# P8_AudioOutput.net
KiCad netlist of a schematic drawn in Altium Designer
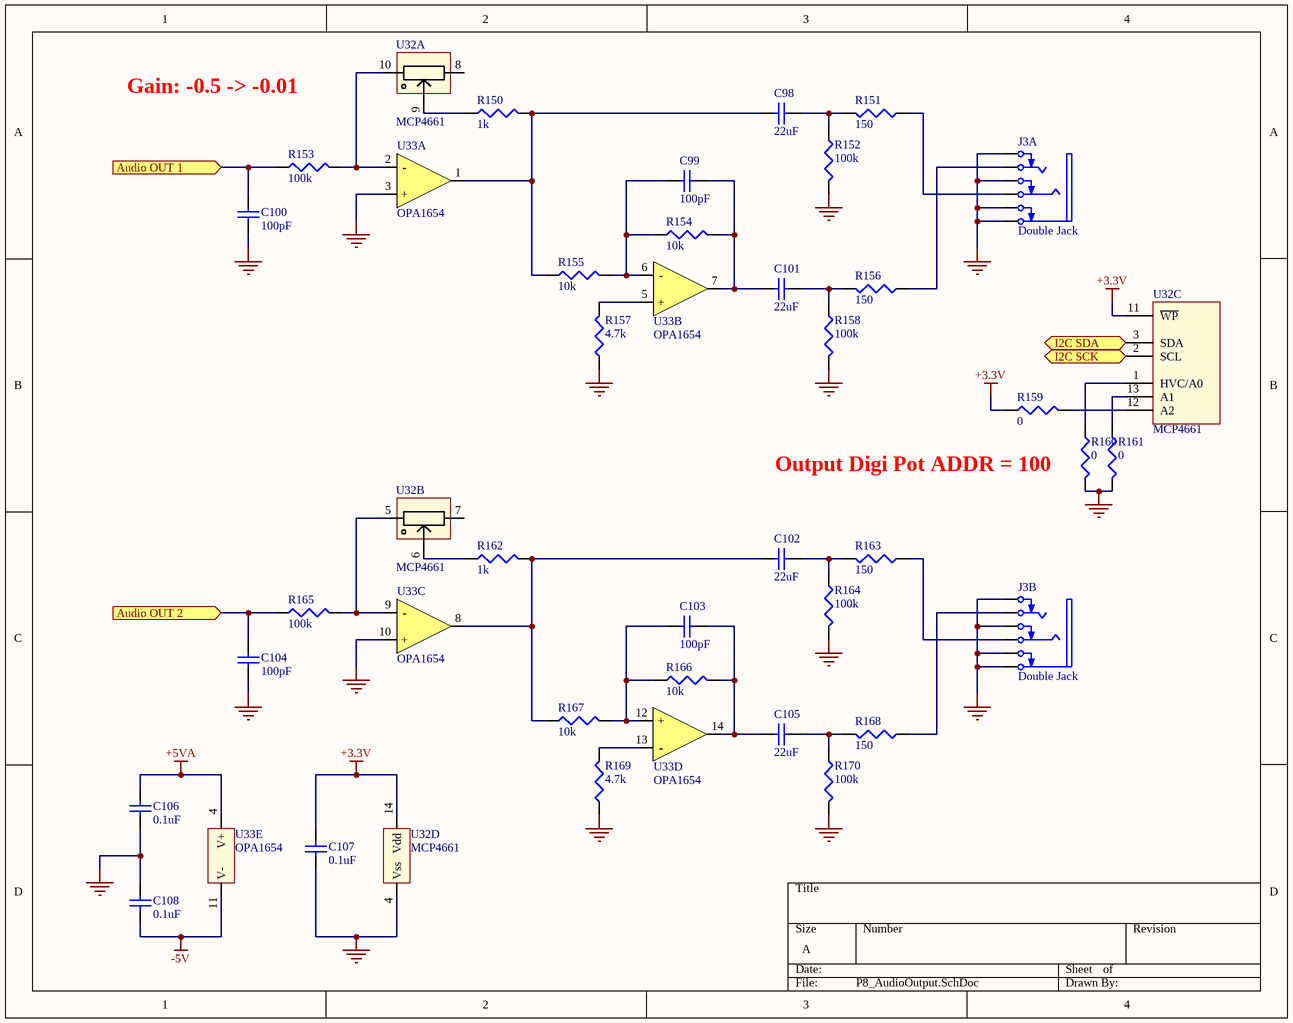
[diagram p0: P8_AudioOutput.SchDoc]

(export (version "E")
  (design (tool "Eeschema 10.0.6"))
  (components
    (comp (ref "C98")
      (value "22uF")
      (footprint "CAP 0603 (1608 metric)")
      (description "Capacitor (Semiconductor SIM Model)")
      (libsource (lib "Miscellaneous Devices") (part "Cap Semi"))
    )
    (comp (ref "C99")
      (value "100pF")
      (footprint "CAP 0603 (1608 metric)")
      (description "Capacitor (Semiconductor SIM Model)")
      (libsource (lib "Miscellaneous Devices") (part "Cap Semi"))
    )
    (comp (ref "C100")
      (value "100pF")
      (footprint "CAP 0603 (1608 metric)")
      (description "Capacitor (Semiconductor SIM Model)")
      (libsource (lib "Miscellaneous Devices") (part "Cap Semi"))
    )
    (comp (ref "C101")
      (value "22uF")
      (footprint "CAP 0603 (1608 metric)")
      (description "Capacitor (Semiconductor SIM Model)")
      (libsource (lib "Miscellaneous Devices") (part "Cap Semi"))
    )
    (comp (ref "C102")
      (value "22uF")
      (footprint "CAP 0603 (1608 metric)")
      (description "Capacitor (Semiconductor SIM Model)")
      (libsource (lib "Miscellaneous Devices") (part "Cap Semi"))
    )
    (comp (ref "C103")
      (value "100pF")
      (footprint "CAP 0603 (1608 metric)")
      (description "Capacitor (Semiconductor SIM Model)")
      (libsource (lib "Miscellaneous Devices") (part "Cap Semi"))
    )
    (comp (ref "C104")
      (value "100pF")
      (footprint "CAP 0603 (1608 metric)")
      (description "Capacitor (Semiconductor SIM Model)")
      (libsource (lib "Miscellaneous Devices") (part "Cap Semi"))
    )
    (comp (ref "C105")
      (value "22uF")
      (footprint "CAP 0603 (1608 metric)")
      (description "Capacitor (Semiconductor SIM Model)")
      (libsource (lib "Miscellaneous Devices") (part "Cap Semi"))
    )
    (comp (ref "C106")
      (value "0.1uF")
      (footprint "CAP 0603 (1608 metric)")
      (description "Capacitor (Semiconductor SIM Model)")
      (libsource (lib "Miscellaneous Devices") (part "Cap Semi"))
    )
    (comp (ref "C107")
      (value "0.1uF")
      (footprint "CAP 0603 (1608 metric)")
      (description "Capacitor (Semiconductor SIM Model)")
      (libsource (lib "Miscellaneous Devices") (part "Cap Semi"))
    )
    (comp (ref "C108")
      (value "0.1uF")
      (footprint "CAP 0603 (1608 metric)")
      (description "Capacitor (Semiconductor SIM Model)")
      (libsource (lib "Miscellaneous Devices") (part "Cap Semi"))
    )
    (comp (ref "J3")
      (value "Double Jack")
      (description "Dual Jack stereo bypassed")
      (libsource (lib "FilterPoC") (part "Dual TRS Jack Bypassed"))
    )
    (comp (ref "R150")
      (value "1k")
      (footprint "RES 0603 (1608 metric)")
      (description "Resistor")
      (libsource (lib "Miscellaneous Devices") (part "Res3"))
    )
    (comp (ref "R151")
      (value "150")
      (footprint "RES 0603 (1608 metric)")
      (description "Resistor")
      (libsource (lib "Miscellaneous Devices") (part "Res3"))
    )
    (comp (ref "R152")
      (value "100k")
      (footprint "RES 0603 (1608 metric)")
      (description "Resistor")
      (libsource (lib "Miscellaneous Devices") (part "Res3"))
    )
    (comp (ref "R153")
      (value "100k")
      (footprint "RES 0603 (1608 metric)")
      (description "Resistor")
      (libsource (lib "Miscellaneous Devices") (part "Res3"))
    )
    (comp (ref "R154")
      (value "10k")
      (footprint "RES 0603 (1608 metric)")
      (description "Resistor")
      (libsource (lib "Miscellaneous Devices") (part "Res3"))
    )
    (comp (ref "R155")
      (value "10k")
      (footprint "RES 0603 (1608 metric)")
      (description "Resistor")
      (libsource (lib "Miscellaneous Devices") (part "Res3"))
    )
    (comp (ref "R156")
      (value "150")
      (footprint "RES 0603 (1608 metric)")
      (description "Resistor")
      (libsource (lib "Miscellaneous Devices") (part "Res3"))
    )
    (comp (ref "R157")
      (value "4.7k")
      (footprint "RES 0603 (1608 metric)")
      (description "Resistor")
      (libsource (lib "Miscellaneous Devices") (part "Res3"))
    )
    (comp (ref "R158")
      (value "100k")
      (footprint "RES 0603 (1608 metric)")
      (description "Resistor")
      (libsource (lib "Miscellaneous Devices") (part "Res3"))
    )
    (comp (ref "R159")
      (value "0")
      (footprint "RES 0603 (1608 metric)")
      (description "Resistor")
      (libsource (lib "Miscellaneous Devices") (part "Res3"))
    )
    (comp (ref "R160")
      (value "0")
      (footprint "RES 0603 (1608 metric)")
      (description "Resistor")
      (libsource (lib "Miscellaneous Devices") (part "Res3"))
    )
    (comp (ref "R161")
      (value "0")
      (footprint "RES 0603 (1608 metric)")
      (description "Resistor")
      (libsource (lib "Miscellaneous Devices") (part "Res3"))
    )
    (comp (ref "R162")
      (value "1k")
      (footprint "RES 0603 (1608 metric)")
      (description "Resistor")
      (libsource (lib "Miscellaneous Devices") (part "Res3"))
    )
    (comp (ref "R163")
      (value "150")
      (footprint "RES 0603 (1608 metric)")
      (description "Resistor")
      (libsource (lib "Miscellaneous Devices") (part "Res3"))
    )
    (comp (ref "R164")
      (value "100k")
      (footprint "RES 0603 (1608 metric)")
      (description "Resistor")
      (libsource (lib "Miscellaneous Devices") (part "Res3"))
    )
    (comp (ref "R165")
      (value "100k")
      (footprint "RES 0603 (1608 metric)")
      (description "Resistor")
      (libsource (lib "Miscellaneous Devices") (part "Res3"))
    )
    (comp (ref "R166")
      (value "10k")
      (footprint "RES 0603 (1608 metric)")
      (description "Resistor")
      (libsource (lib "Miscellaneous Devices") (part "Res3"))
    )
    (comp (ref "R167")
      (value "10k")
      (footprint "RES 0603 (1608 metric)")
      (description "Resistor")
      (libsource (lib "Miscellaneous Devices") (part "Res3"))
    )
    (comp (ref "R168")
      (value "150")
      (footprint "RES 0603 (1608 metric)")
      (description "Resistor")
      (libsource (lib "Miscellaneous Devices") (part "Res3"))
    )
    (comp (ref "R169")
      (value "4.7k")
      (footprint "RES 0603 (1608 metric)")
      (description "Resistor")
      (libsource (lib "Miscellaneous Devices") (part "Res3"))
    )
    (comp (ref "R170")
      (value "100k")
      (footprint "RES 0603 (1608 metric)")
      (description "Resistor")
      (libsource (lib "Miscellaneous Devices") (part "Res3"))
    )
    (comp (ref "U32")
      (value "MCP4661")
      (description "Dual DigiPot non volatile I2C")
      (libsource (lib "FilterPoC") (part "MCP4661"))
    )
    (comp (ref "U33")
      (value "OPA1654")
      (description "Quad Audio OpAmp")
      (libsource (lib "") (part "OPA1654_1"))
    )
  )
  (nets
    (net (code "1") (name "+3.3V") (class "Default")
      (node (ref "C107") (pin "1") (pinfunction "1_1") (pintype "passive"))
      (node (ref "R159") (pin "1") (pinfunction "1_1") (pintype "passive"))
      (node (ref "U32") (pin "11") (pinfunction "~{WP}_11") (pintype "passive"))
      (node (ref "U32") (pin "14") (pinfunction "Vdd_14") (pintype "power_in"))
    )
    (net (code "2") (name "+5VA") (class "Default")
      (node (ref "C106") (pin "1") (pinfunction "1_1") (pintype "passive"))
      (node (ref "U33") (pin "4") (pinfunction "V+_4") (pintype "power_in"))
    )
    (net (code "3") (name "-5V") (class "Default")
      (node (ref "C108") (pin "2") (pinfunction "2_2") (pintype "passive"))
      (node (ref "U33") (pin "11") (pinfunction "V-_11") (pintype "power_in"))
    )
    (net (code "4") (name "/Audio OUT 1") (class "Default")
      (node (ref "C100") (pin "2") (pinfunction "2_2") (pintype "passive"))
      (node (ref "R153") (pin "1") (pinfunction "1_1") (pintype "passive"))
    )
    (net (code "5") (name "/Audio OUT 2") (class "Default")
      (node (ref "C104") (pin "2") (pinfunction "2_2") (pintype "passive"))
      (node (ref "R165") (pin "1") (pinfunction "1_1") (pintype "passive"))
    )
    (net (code "6") (name "/I2C SCK") (class "Default")
      (node (ref "U32") (pin "2") (pinfunction "SCL_2") (pintype "passive"))
    )
    (net (code "7") (name "/I2C SDA") (class "Default")
      (node (ref "U32") (pin "3") (pinfunction "SDA_3") (pintype "passive"))
    )
    (net (code "8") (name "GND") (class "Default")
      (node (ref "C100") (pin "1") (pinfunction "1_1") (pintype "passive"))
      (node (ref "C104") (pin "1") (pinfunction "1_1") (pintype "passive"))
      (node (ref "C106") (pin "2") (pinfunction "2_2") (pintype "passive"))
      (node (ref "C107") (pin "2") (pinfunction "2_2") (pintype "passive"))
      (node (ref "C108") (pin "1") (pinfunction "1_1") (pintype "passive"))
      (node (ref "J3") (pin "1") (pinfunction "SB_1") (pintype "passive"))
      (node (ref "J3") (pin "10") (pinfunction "S_10") (pintype "power_in"))
      (node (ref "J3") (pin "2") (pinfunction "RB_2") (pintype "passive"))
      (node (ref "J3") (pin "3") (pinfunction "TB_3") (pintype "passive"))
      (node (ref "J3") (pin "4") (pinfunction "S_4") (pintype "power_in"))
      (node (ref "J3") (pin "7") (pinfunction "SB_7") (pintype "passive"))
      (node (ref "J3") (pin "8") (pinfunction "RB_8") (pintype "passive"))
      (node (ref "J3") (pin "9") (pinfunction "TB_9") (pintype "passive"))
      (node (ref "R152") (pin "2") (pinfunction "2_2") (pintype "passive"))
      (node (ref "R157") (pin "1") (pinfunction "1_1") (pintype "passive"))
      (node (ref "R158") (pin "2") (pinfunction "2_2") (pintype "passive"))
      (node (ref "R160") (pin "2") (pinfunction "2_2") (pintype "passive"))
      (node (ref "R161") (pin "2") (pinfunction "2_2") (pintype "passive"))
      (node (ref "R164") (pin "2") (pinfunction "2_2") (pintype "passive"))
      (node (ref "R169") (pin "1") (pinfunction "1_1") (pintype "passive"))
      (node (ref "R170") (pin "2") (pinfunction "2_2") (pintype "passive"))
      (node (ref "U32") (pin "4") (pinfunction "Vss_4") (pintype "power_in"))
      (node (ref "U33") (pin "10") (pinfunction "+_10") (pintype "passive"))
      (node (ref "U33") (pin "3") (pinfunction "+_3") (pintype "passive"))
    )
    (net (code "9") (name "Net-(C98-Pad1)") (class "Default")
      (node (ref "C98") (pin "1") (pinfunction "1_1") (pintype "passive"))
      (node (ref "R151") (pin "2") (pinfunction "2_2") (pintype "passive"))
      (node (ref "R152") (pin "1") (pinfunction "1_1") (pintype "passive"))
    )
    (net (code "10") (name "Net-(C101-Pad1)") (class "Default")
      (node (ref "C101") (pin "1") (pinfunction "1_1") (pintype "passive"))
      (node (ref "R156") (pin "2") (pinfunction "2_2") (pintype "passive"))
      (node (ref "R158") (pin "1") (pinfunction "1_1") (pintype "passive"))
    )
    (net (code "11") (name "Net-(C102-Pad1)") (class "Default")
      (node (ref "C102") (pin "1") (pinfunction "1_1") (pintype "passive"))
      (node (ref "R163") (pin "2") (pinfunction "2_2") (pintype "passive"))
      (node (ref "R164") (pin "1") (pinfunction "1_1") (pintype "passive"))
    )
    (net (code "12") (name "Net-(C105-Pad1)") (class "Default")
      (node (ref "C105") (pin "1") (pinfunction "1_1") (pintype "passive"))
      (node (ref "R168") (pin "2") (pinfunction "2_2") (pintype "passive"))
      (node (ref "R170") (pin "1") (pinfunction "1_1") (pintype "passive"))
    )
    (net (code "13") (name "Net-(J3A-R)") (class "Default")
      (node (ref "J3") (pin "11") (pinfunction "R_11") (pintype "passive"))
      (node (ref "R151") (pin "1") (pinfunction "1_1") (pintype "passive"))
    )
    (net (code "14") (name "Net-(J3A-T)") (class "Default")
      (node (ref "J3") (pin "12") (pinfunction "T_12") (pintype "passive"))
      (node (ref "R156") (pin "1") (pinfunction "1_1") (pintype "passive"))
    )
    (net (code "15") (name "Net-(J3B-R)") (class "Default")
      (node (ref "J3") (pin "5") (pinfunction "R_5") (pintype "passive"))
      (node (ref "R163") (pin "1") (pinfunction "1_1") (pintype "passive"))
    )
    (net (code "16") (name "Net-(J3B-T)") (class "Default")
      (node (ref "J3") (pin "6") (pinfunction "T_6") (pintype "passive"))
      (node (ref "R168") (pin "1") (pinfunction "1_1") (pintype "passive"))
    )
    (net (code "17") (name "Net-(U32A-P0B)") (class "Default")
      (node (ref "R153") (pin "2") (pinfunction "2_2") (pintype "passive"))
      (node (ref "U32") (pin "10") (pinfunction "P0B_10") (pintype "passive"))
      (node (ref "U33") (pin "2") (pinfunction "-_2") (pintype "passive"))
    )
    (net (code "18") (name "Net-(U32A-P0W)") (class "Default")
      (node (ref "R150") (pin "1") (pinfunction "1_1") (pintype "passive"))
      (node (ref "U32") (pin "9") (pinfunction "P0W_9") (pintype "passive"))
    )
    (net (code "19") (name "Net-(U32B-P1B)") (class "Default")
      (node (ref "R165") (pin "2") (pinfunction "2_2") (pintype "passive"))
      (node (ref "U32") (pin "5") (pinfunction "P1B_5") (pintype "passive"))
      (node (ref "U33") (pin "9") (pinfunction "-_9") (pintype "passive"))
    )
    (net (code "20") (name "Net-(U32B-P1W)") (class "Default")
      (node (ref "R162") (pin "1") (pinfunction "1_1") (pintype "passive"))
      (node (ref "U32") (pin "6") (pinfunction "P1W_6") (pintype "passive"))
    )
    (net (code "21") (name "Net-(U32C-A1)") (class "Default")
      (node (ref "R161") (pin "1") (pinfunction "1_1") (pintype "passive"))
      (node (ref "U32") (pin "13") (pinfunction "A1_13") (pintype "power_in"))
    )
    (net (code "22") (name "Net-(U32C-A2)") (class "Default")
      (node (ref "R159") (pin "2") (pinfunction "2_2") (pintype "passive"))
      (node (ref "U32") (pin "12") (pinfunction "A2_12") (pintype "power_in"))
    )
    (net (code "23") (name "Net-(U32C-HVC{slash}A0)") (class "Default")
      (node (ref "R160") (pin "1") (pinfunction "1_1") (pintype "passive"))
      (node (ref "U32") (pin "1") (pinfunction "HVC/A0_1") (pintype "power_in"))
    )
    (net (code "24") (name "Net-(U33A-OUT)") (class "Default")
      (node (ref "C98") (pin "2") (pinfunction "2_2") (pintype "passive"))
      (node (ref "R150") (pin "2") (pinfunction "2_2") (pintype "passive"))
      (node (ref "R155") (pin "1") (pinfunction "1_1") (pintype "passive"))
      (node (ref "U33") (pin "1") (pinfunction "OUT_1") (pintype "passive"))
    )
    (net (code "25") (name "Net-(U33B-+)") (class "Default")
      (node (ref "R157") (pin "2") (pinfunction "2_2") (pintype "passive"))
      (node (ref "U33") (pin "5") (pinfunction "+_5") (pintype "passive"))
    )
    (net (code "26") (name "Net-(U33B--)") (class "Default")
      (node (ref "C99") (pin "2") (pinfunction "2_2") (pintype "passive"))
      (node (ref "R154") (pin "1") (pinfunction "1_1") (pintype "passive"))
      (node (ref "R155") (pin "2") (pinfunction "2_2") (pintype "passive"))
      (node (ref "U33") (pin "6") (pinfunction "-_6") (pintype "passive"))
    )
    (net (code "27") (name "Net-(U33B-OUT)") (class "Default")
      (node (ref "C101") (pin "2") (pinfunction "2_2") (pintype "passive"))
      (node (ref "C99") (pin "1") (pinfunction "1_1") (pintype "passive"))
      (node (ref "R154") (pin "2") (pinfunction "2_2") (pintype "passive"))
      (node (ref "U33") (pin "7") (pinfunction "OUT_7") (pintype "passive"))
    )
    (net (code "28") (name "Net-(U33C-OUT)") (class "Default")
      (node (ref "C102") (pin "2") (pinfunction "2_2") (pintype "passive"))
      (node (ref "R162") (pin "2") (pinfunction "2_2") (pintype "passive"))
      (node (ref "R167") (pin "1") (pinfunction "1_1") (pintype "passive"))
      (node (ref "U33") (pin "8") (pinfunction "OUT_8") (pintype "passive"))
    )
    (net (code "29") (name "Net-(U33D-+)") (class "Default")
      (node (ref "C103") (pin "2") (pinfunction "2_2") (pintype "passive"))
      (node (ref "R166") (pin "1") (pinfunction "1_1") (pintype "passive"))
      (node (ref "R167") (pin "2") (pinfunction "2_2") (pintype "passive"))
      (node (ref "U33") (pin "12") (pinfunction "+_12") (pintype "passive"))
    )
    (net (code "30") (name "Net-(U33D--)") (class "Default")
      (node (ref "R169") (pin "2") (pinfunction "2_2") (pintype "passive"))
      (node (ref "U33") (pin "13") (pinfunction "-_13") (pintype "passive"))
    )
    (net (code "31") (name "Net-(U33D-OUT)") (class "Default")
      (node (ref "C103") (pin "1") (pinfunction "1_1") (pintype "passive"))
      (node (ref "C105") (pin "2") (pinfunction "2_2") (pintype "passive"))
      (node (ref "R166") (pin "2") (pinfunction "2_2") (pintype "passive"))
      (node (ref "U33") (pin "14") (pinfunction "OUT_14") (pintype "passive"))
    )
    (net (code "32") (name "unconnected-(U32A-P0A-Pad8)") (class "Default")
      (node (ref "U32") (pin "8") (pinfunction "P0A_8") (pintype "passive"))
    )
    (net (code "33") (name "unconnected-(U32B-P1A-Pad7)") (class "Default")
      (node (ref "U32") (pin "7") (pinfunction "P1A_7") (pintype "passive"))
    )
  )
)
